# board.net
KiCad netlist of a schematic drawn in EAGLE
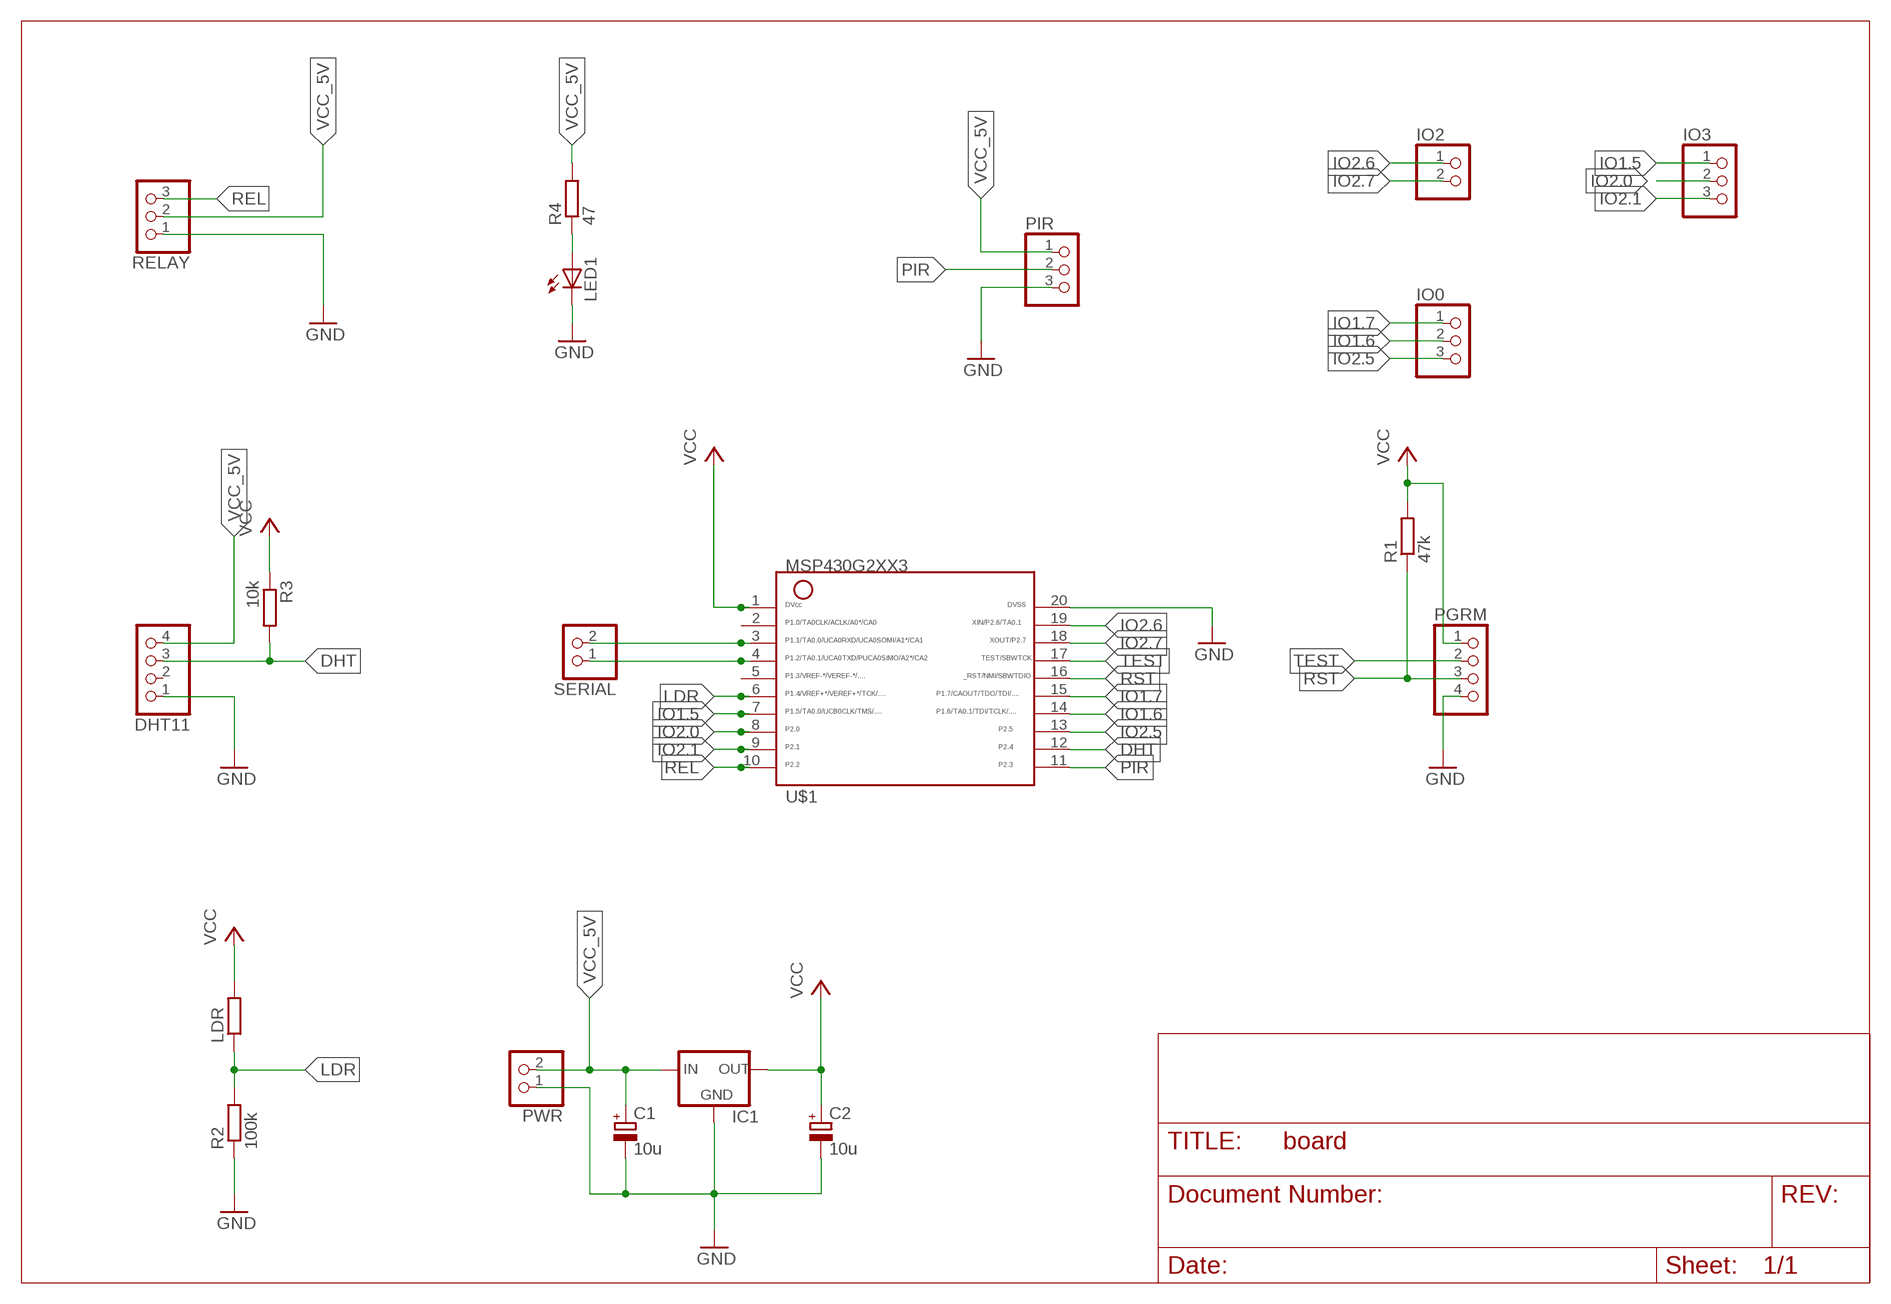
[diagram p0: schematic, sheet 1]

(export (version "E")
  (design (tool "Eeschema 10.0.6"))
  (components
    (comp (ref "C1")
      (value "10u")
      (footprint "eagle-import:E2,5-5")
      (libsource (lib "eagle-import") (part "CPOL-EUE2.5-5"))
    )
    (comp (ref "C2")
      (value "10u")
      (footprint "eagle-import:E2,5-5")
      (libsource (lib "eagle-import") (part "CPOL-EUE2.5-5"))
    )
    (comp (ref "DHT11")
      (value "PINHD-1X4")
      (footprint "eagle-import:1X04")
      (libsource (lib "eagle-import") (part "PINHD-1X4"))
    )
    (comp (ref "IC1")
      (value "MCP1700TRI")
      (footprint "eagle-import:TO92")
      (libsource (lib "eagle-import") (part "MCP1700TRI"))
    )
    (comp (ref "IO0")
      (value "PINHD-1X3")
      (footprint "eagle-import:1X03")
      (libsource (lib "eagle-import") (part "PINHD-1X3"))
    )
    (comp (ref "IO2")
      (value "PINHD-1X2")
      (footprint "eagle-import:1X02")
      (libsource (lib "eagle-import") (part "PINHD-1X2"))
    )
    (comp (ref "IO3")
      (value "PINHD-1X3")
      (footprint "eagle-import:1X03")
      (libsource (lib "eagle-import") (part "PINHD-1X3"))
    )
    (comp (ref "LDR")
      (value "R-EU_0207/5V")
      (footprint "eagle-import:0207_5V")
      (libsource (lib "eagle-import") (part "R-EU_0207/5V"))
    )
    (comp (ref "LED1")
      (value "LED3MM")
      (footprint "eagle-import:LED3MM")
      (libsource (lib "eagle-import") (part "LED3MM"))
    )
    (comp (ref "PGRM")
      (value "PINHD-1X4")
      (footprint "eagle-import:1X04")
      (libsource (lib "eagle-import") (part "PINHD-1X4"))
    )
    (comp (ref "PIR")
      (value "PINHD-1X3")
      (footprint "eagle-import:1X03")
      (libsource (lib "eagle-import") (part "PINHD-1X3"))
    )
    (comp (ref "PWR")
      (value "PINHD-1X2")
      (footprint "eagle-import:1X02")
      (libsource (lib "eagle-import") (part "PINHD-1X2"))
    )
    (comp (ref "R1")
      (value "47k")
      (footprint "eagle-import:0207_10")
      (libsource (lib "eagle-import") (part "R-EU_0207/10"))
    )
    (comp (ref "R2")
      (value "100k")
      (footprint "eagle-import:0207_10")
      (libsource (lib "eagle-import") (part "R-EU_0207/10"))
    )
    (comp (ref "R3")
      (value "10k")
      (footprint "eagle-import:0207_10")
      (libsource (lib "eagle-import") (part "R-EU_0207/10"))
    )
    (comp (ref "R4")
      (value "47")
      (footprint "eagle-import:0207_10")
      (libsource (lib "eagle-import") (part "R-EU_0207/10"))
    )
    (comp (ref "RELAY")
      (value "PINHD-1X3")
      (footprint "eagle-import:1X03")
      (libsource (lib "eagle-import") (part "PINHD-1X3"))
    )
    (comp (ref "SERIAL")
      (value "PINHD-1X2")
      (footprint "eagle-import:1X02")
      (libsource (lib "eagle-import") (part "PINHD-1X2"))
    )
    (comp (ref "U$1")
      (value "G2XX3---N20")
      (footprint "eagle-import:N20")
      (libsource (lib "eagle-import") (part "G2XX3---N20"))
    )
  )
  (nets
    (net (code "1") (name "DHT") (class "Default")
      (node (ref "DHT11") (pin "3") (pinfunction "3_3") (pintype "passive"))
      (node (ref "R3") (pin "2") (pinfunction "2_2") (pintype "passive"))
      (node (ref "U$1") (pin "12") (pinfunction "12_12") (pintype "bidirectional"))
    )
    (net (code "2") (name "GND") (class "Default")
      (node (ref "C1") (pin "-") (pinfunction "-_-") (pintype "passive"))
      (node (ref "C2") (pin "-") (pinfunction "-_-") (pintype "passive"))
      (node (ref "DHT11") (pin "1") (pinfunction "1_1") (pintype "passive"))
      (node (ref "IC1") (pin "1") (pinfunction "GND_1") (pintype "input"))
      (node (ref "LED1") (pin "K") (pinfunction "C_K") (pintype "passive"))
      (node (ref "PGRM") (pin "4") (pinfunction "4_4") (pintype "passive"))
      (node (ref "PIR") (pin "3") (pinfunction "3_3") (pintype "passive"))
      (node (ref "PWR") (pin "1") (pinfunction "1_1") (pintype "passive"))
      (node (ref "R2") (pin "1") (pinfunction "1_1") (pintype "passive"))
      (node (ref "RELAY") (pin "1") (pinfunction "1_1") (pintype "passive"))
      (node (ref "U$1") (pin "20") (pinfunction "20_20") (pintype "bidirectional"))
    )
    (net (code "3") (name "IO1.5") (class "Default")
      (node (ref "IO3") (pin "1") (pinfunction "1_1") (pintype "passive"))
      (node (ref "U$1") (pin "7") (pinfunction "7_7") (pintype "bidirectional"))
    )
    (net (code "4") (name "IO1.6") (class "Default")
      (node (ref "IO0") (pin "2") (pinfunction "2_2") (pintype "passive"))
      (node (ref "U$1") (pin "14") (pinfunction "14_14") (pintype "bidirectional"))
    )
    (net (code "5") (name "IO1.7") (class "Default")
      (node (ref "IO0") (pin "1") (pinfunction "1_1") (pintype "passive"))
      (node (ref "U$1") (pin "15") (pinfunction "15_15") (pintype "bidirectional"))
    )
    (net (code "6") (name "IO2.0") (class "Default")
      (node (ref "IO3") (pin "2") (pinfunction "2_2") (pintype "passive"))
      (node (ref "U$1") (pin "8") (pinfunction "8_8") (pintype "bidirectional"))
    )
    (net (code "7") (name "IO2.1") (class "Default")
      (node (ref "IO3") (pin "3") (pinfunction "3_3") (pintype "passive"))
      (node (ref "U$1") (pin "9") (pinfunction "9_9") (pintype "bidirectional"))
    )
    (net (code "8") (name "IO2.5") (class "Default")
      (node (ref "IO0") (pin "3") (pinfunction "3_3") (pintype "passive"))
      (node (ref "U$1") (pin "13") (pinfunction "13_13") (pintype "bidirectional"))
    )
    (net (code "9") (name "IO2.6") (class "Default")
      (node (ref "IO2") (pin "1") (pinfunction "1_1") (pintype "passive"))
      (node (ref "U$1") (pin "19") (pinfunction "19_19") (pintype "bidirectional"))
    )
    (net (code "10") (name "IO2.7") (class "Default")
      (node (ref "IO2") (pin "2") (pinfunction "2_2") (pintype "passive"))
      (node (ref "U$1") (pin "18") (pinfunction "18_18") (pintype "bidirectional"))
    )
    (net (code "11") (name "LDR") (class "Default")
      (node (ref "LDR") (pin "1") (pinfunction "1_1") (pintype "passive"))
      (node (ref "R2") (pin "2") (pinfunction "2_2") (pintype "passive"))
      (node (ref "U$1") (pin "6") (pinfunction "6_6") (pintype "bidirectional"))
    )
    (net (code "12") (name "Net-(LED1-PadA)") (class "Default")
      (node (ref "LED1") (pin "A") (pinfunction "A_A") (pintype "passive"))
      (node (ref "R4") (pin "1") (pinfunction "1_1") (pintype "passive"))
    )
    (net (code "13") (name "Net-(SERIAL-Pad1)") (class "Default")
      (node (ref "SERIAL") (pin "1") (pinfunction "1_1") (pintype "passive"))
      (node (ref "U$1") (pin "4") (pinfunction "4_4") (pintype "bidirectional"))
    )
    (net (code "14") (name "Net-(SERIAL-Pad2)") (class "Default")
      (node (ref "SERIAL") (pin "2") (pinfunction "2_2") (pintype "passive"))
      (node (ref "U$1") (pin "3") (pinfunction "3_3") (pintype "bidirectional"))
    )
    (net (code "15") (name "PIR") (class "Default")
      (node (ref "PIR") (pin "2") (pinfunction "2_2") (pintype "passive"))
      (node (ref "U$1") (pin "11") (pinfunction "11_11") (pintype "bidirectional"))
    )
    (net (code "16") (name "REL") (class "Default")
      (node (ref "RELAY") (pin "3") (pinfunction "3_3") (pintype "passive"))
      (node (ref "U$1") (pin "10") (pinfunction "10_10") (pintype "bidirectional"))
    )
    (net (code "17") (name "RST") (class "Default")
      (node (ref "PGRM") (pin "3") (pinfunction "3_3") (pintype "passive"))
      (node (ref "R1") (pin "1") (pinfunction "1_1") (pintype "passive"))
      (node (ref "U$1") (pin "16") (pinfunction "16_16") (pintype "bidirectional"))
    )
    (net (code "18") (name "TEST") (class "Default")
      (node (ref "PGRM") (pin "2") (pinfunction "2_2") (pintype "passive"))
      (node (ref "U$1") (pin "17") (pinfunction "17_17") (pintype "bidirectional"))
    )
    (net (code "19") (name "VCC") (class "Default")
      (node (ref "C2") (pin "+") (pinfunction "+_+") (pintype "passive"))
      (node (ref "IC1") (pin "3") (pinfunction "OUT_3") (pintype "passive"))
      (node (ref "LDR") (pin "2") (pinfunction "2_2") (pintype "passive"))
      (node (ref "PGRM") (pin "1") (pinfunction "1_1") (pintype "passive"))
      (node (ref "R1") (pin "2") (pinfunction "2_2") (pintype "passive"))
      (node (ref "R3") (pin "1") (pinfunction "1_1") (pintype "passive"))
      (node (ref "U$1") (pin "1") (pinfunction "1_1") (pintype "bidirectional"))
    )
    (net (code "20") (name "VCC_5V") (class "Default")
      (node (ref "C1") (pin "+") (pinfunction "+_+") (pintype "passive"))
      (node (ref "DHT11") (pin "4") (pinfunction "4_4") (pintype "passive"))
      (node (ref "IC1") (pin "2") (pinfunction "IN_2") (pintype "input"))
      (node (ref "PIR") (pin "1") (pinfunction "1_1") (pintype "passive"))
      (node (ref "PWR") (pin "2") (pinfunction "2_2") (pintype "passive"))
      (node (ref "R4") (pin "2") (pinfunction "2_2") (pintype "passive"))
      (node (ref "RELAY") (pin "2") (pinfunction "2_2") (pintype "passive"))
    )
    (net (code "21") (name "unconnected-(DHT11-Pad2)") (class "Default")
      (node (ref "DHT11") (pin "2") (pinfunction "2_2") (pintype "passive"))
    )
    (net (code "22") (name "unconnected-(U$1-Pad2)") (class "Default")
      (node (ref "U$1") (pin "2") (pinfunction "2_2") (pintype "bidirectional"))
    )
    (net (code "23") (name "unconnected-(U$1-Pad5)") (class "Default")
      (node (ref "U$1") (pin "5") (pinfunction "5_5") (pintype "bidirectional"))
    )
  )
)
